# Controller_Board_Interface.net
KiCad netlist of a schematic drawn in Altium Designer
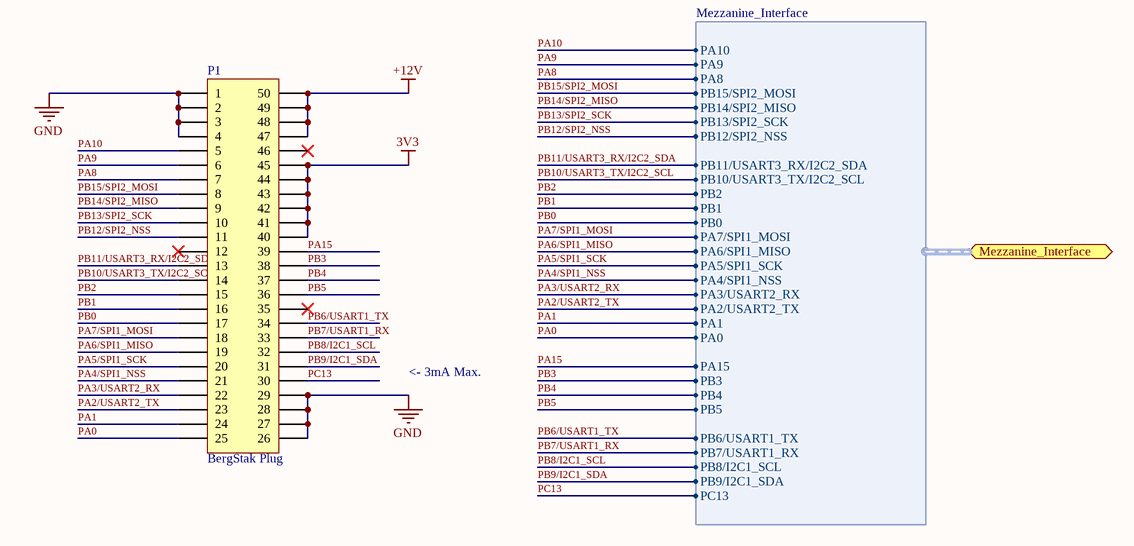
[diagram p0: Controller_Board_Interface.SchDoc]

(export (version "E")
  (design (tool "Eeschema 10.0.6"))
  (components
    (comp (ref "P1")
      (value "CONN 50POS Bergstak Plug 0.02\"")
      (footprint "CONN, Bergstak 50 Pos Plug")
      (description "50 Position Connector Plug, Outer Shroud Contacts Surface Mount Gold")
      (fields (field (name "SERIES") "BergStak Plug"))
      (libsource (lib "Schematic Diagrams") (part "CONN 50POS Bergstak Plug 0.02{dblquote}"))
    )
  )
  (nets
    (net (code "2") (name "+12V") (class "Default")
      (node (ref "P1") (pin "47") (pinfunction "47_47") (pintype "passive"))
      (node (ref "P1") (pin "48") (pinfunction "48_48") (pintype "passive"))
      (node (ref "P1") (pin "49") (pinfunction "49_49") (pintype "passive"))
      (node (ref "P1") (pin "50") (pinfunction "50_50") (pintype "passive"))
    )
    (net (code "3") (name "/PA0") (class "Default")
      (node (ref "P1") (pin "25") (pinfunction "25_25") (pintype "passive"))
    )
    (net (code "4") (name "/PA1") (class "Default")
      (node (ref "P1") (pin "24") (pinfunction "24_24") (pintype "passive"))
    )
    (net (code "5") (name "/PA2{slash}USART2_TX") (class "Default")
      (node (ref "P1") (pin "23") (pinfunction "23_23") (pintype "passive"))
    )
    (net (code "6") (name "/PA3{slash}USART2_RX") (class "Default")
      (node (ref "P1") (pin "22") (pinfunction "22_22") (pintype "passive"))
    )
    (net (code "7") (name "/PA4{slash}SPI1_NSS") (class "Default")
      (node (ref "P1") (pin "21") (pinfunction "21_21") (pintype "passive"))
    )
    (net (code "8") (name "/PA5{slash}SPI1_SCK") (class "Default")
      (node (ref "P1") (pin "20") (pinfunction "20_20") (pintype "passive"))
    )
    (net (code "9") (name "/PA6{slash}SPI1_MISO") (class "Default")
      (node (ref "P1") (pin "19") (pinfunction "19_19") (pintype "passive"))
    )
    (net (code "10") (name "/PA7{slash}SPI1_MOSI") (class "Default")
      (node (ref "P1") (pin "18") (pinfunction "18_18") (pintype "passive"))
    )
    (net (code "11") (name "/PA8") (class "Default")
      (node (ref "P1") (pin "7") (pinfunction "7_7") (pintype "passive"))
    )
    (net (code "12") (name "/PA9") (class "Default")
      (node (ref "P1") (pin "6") (pinfunction "6_6") (pintype "passive"))
    )
    (net (code "13") (name "/PA10") (class "Default")
      (node (ref "P1") (pin "5") (pinfunction "5_5") (pintype "passive"))
    )
    (net (code "14") (name "/PA15") (class "Default")
      (node (ref "P1") (pin "39") (pinfunction "39_39") (pintype "passive"))
    )
    (net (code "15") (name "/PB0") (class "Default")
      (node (ref "P1") (pin "17") (pinfunction "17_17") (pintype "passive"))
    )
    (net (code "16") (name "/PB1") (class "Default")
      (node (ref "P1") (pin "16") (pinfunction "16_16") (pintype "passive"))
    )
    (net (code "17") (name "/PB2") (class "Default")
      (node (ref "P1") (pin "15") (pinfunction "15_15") (pintype "passive"))
    )
    (net (code "18") (name "/PB3") (class "Default")
      (node (ref "P1") (pin "38") (pinfunction "38_38") (pintype "passive"))
    )
    (net (code "19") (name "/PB4") (class "Default")
      (node (ref "P1") (pin "37") (pinfunction "37_37") (pintype "passive"))
    )
    (net (code "20") (name "/PB5") (class "Default")
      (node (ref "P1") (pin "36") (pinfunction "36_36") (pintype "passive"))
    )
    (net (code "21") (name "/PB6{slash}USART1_TX") (class "Default")
      (node (ref "P1") (pin "34") (pinfunction "34_34") (pintype "passive"))
    )
    (net (code "22") (name "/PB7{slash}USART1_RX") (class "Default")
      (node (ref "P1") (pin "33") (pinfunction "33_33") (pintype "passive"))
    )
    (net (code "23") (name "/PB8{slash}I2C1_SCL") (class "Default")
      (node (ref "P1") (pin "32") (pinfunction "32_32") (pintype "passive"))
    )
    (net (code "24") (name "/PB9{slash}I2C1_SDA") (class "Default")
      (node (ref "P1") (pin "31") (pinfunction "31_31") (pintype "passive"))
    )
    (net (code "25") (name "/PB10{slash}USART3_TX{slash}I2C2_SCL") (class "Default")
      (node (ref "P1") (pin "14") (pinfunction "14_14") (pintype "passive"))
    )
    (net (code "26") (name "/PB11{slash}USART3_RX{slash}I2C2_SDA") (class "Default")
      (node (ref "P1") (pin "13") (pinfunction "13_13") (pintype "passive"))
    )
    (net (code "27") (name "/PB12{slash}SPI2_NSS") (class "Default")
      (node (ref "P1") (pin "11") (pinfunction "11_11") (pintype "passive"))
    )
    (net (code "28") (name "/PB13{slash}SPI2_SCK") (class "Default")
      (node (ref "P1") (pin "10") (pinfunction "10_10") (pintype "passive"))
    )
    (net (code "29") (name "/PB14{slash}SPI2_MISO") (class "Default")
      (node (ref "P1") (pin "9") (pinfunction "9_9") (pintype "passive"))
    )
    (net (code "30") (name "/PB15{slash}SPI2_MOSI") (class "Default")
      (node (ref "P1") (pin "8") (pinfunction "8_8") (pintype "passive"))
    )
    (net (code "31") (name "/PC13") (class "Default")
      (node (ref "P1") (pin "30") (pinfunction "30_30") (pintype "passive"))
    )
    (net (code "33") (name "3V3") (class "Default")
      (node (ref "P1") (pin "40") (pinfunction "40_40") (pintype "passive"))
      (node (ref "P1") (pin "41") (pinfunction "41_41") (pintype "passive"))
      (node (ref "P1") (pin "42") (pinfunction "42_42") (pintype "passive"))
      (node (ref "P1") (pin "43") (pinfunction "43_43") (pintype "passive"))
      (node (ref "P1") (pin "44") (pinfunction "44_44") (pintype "passive"))
      (node (ref "P1") (pin "45") (pinfunction "45_45") (pintype "passive"))
    )
    (net (code "34") (name "GND") (class "Default")
      (node (ref "P1") (pin "1") (pinfunction "1_1") (pintype "passive"))
      (node (ref "P1") (pin "2") (pinfunction "2_2") (pintype "passive"))
      (node (ref "P1") (pin "26") (pinfunction "26_26") (pintype "passive"))
      (node (ref "P1") (pin "27") (pinfunction "27_27") (pintype "passive"))
      (node (ref "P1") (pin "28") (pinfunction "28_28") (pintype "passive"))
      (node (ref "P1") (pin "29") (pinfunction "29_29") (pintype "passive"))
      (node (ref "P1") (pin "3") (pinfunction "3_3") (pintype "passive"))
      (node (ref "P1") (pin "4") (pinfunction "4_4") (pintype "passive"))
    )
    (net (code "35") (name "unconnected-(P1-Pad12)") (class "Default")
      (node (ref "P1") (pin "12") (pinfunction "12_12") (pintype "passive+no_connect"))
    )
    (net (code "36") (name "unconnected-(P1-Pad35)") (class "Default")
      (node (ref "P1") (pin "35") (pinfunction "35_35") (pintype "passive+no_connect"))
    )
    (net (code "37") (name "unconnected-(P1-Pad46)") (class "Default")
      (node (ref "P1") (pin "46") (pinfunction "46_46") (pintype "passive+no_connect"))
    )
  )
)
